# R2D2_Remote.net
KiCad netlist of a schematic drawn in EAGLE
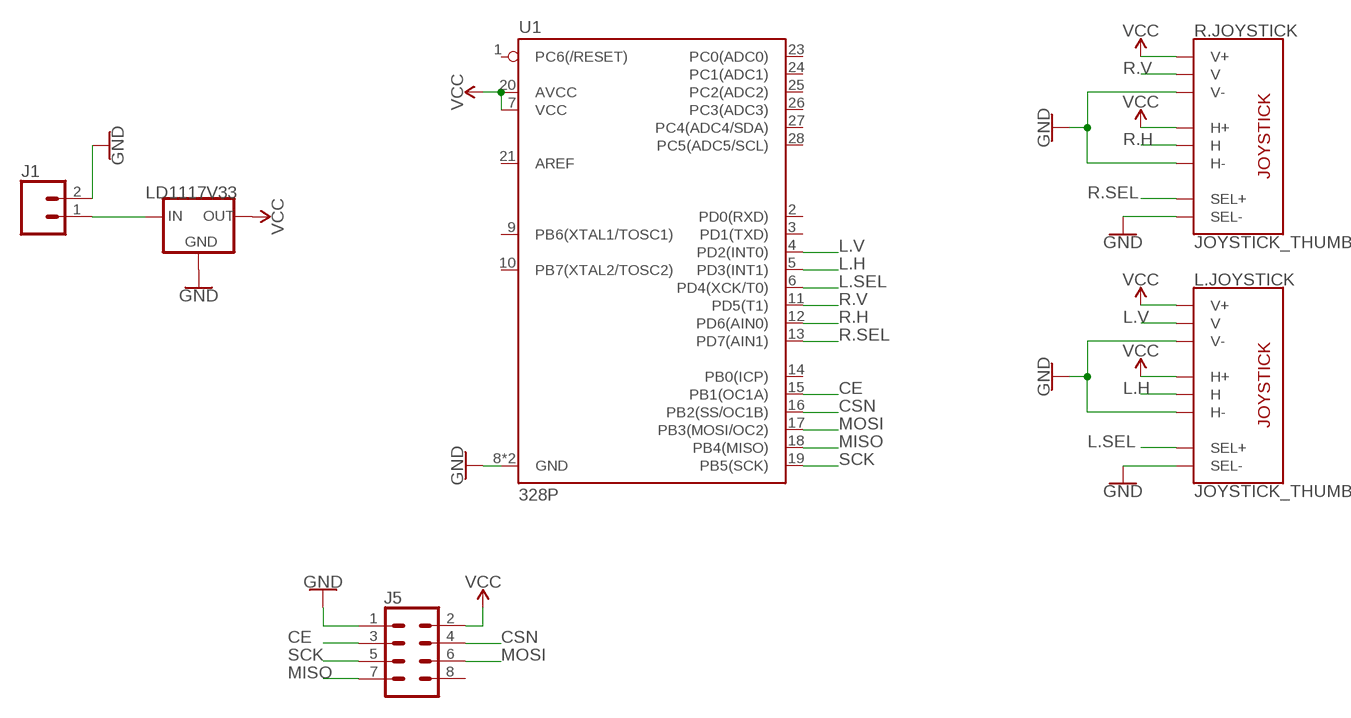
[diagram p0: schematic, sheet 1]

(export (version "E")
  (design (tool "Eeschema 10.0.6"))
  (components
    (comp (ref "J1")
      (value "CONN_02")
      (footprint "eagle-import:1X02")
      (libsource (lib "eagle-import") (part "CONN_02"))
    )
    (comp (ref "J5")
      (value "CONN_04X2")
      (footprint "eagle-import:2X4")
      (libsource (lib "eagle-import") (part "CONN_04X2"))
    )
    (comp (ref "L.JOYSTICK")
      (value "JOYSTICK_THUMB")
      (footprint "eagle-import:JOYSTICK")
      (libsource (lib "eagle-import") (part "JOYSTICK_THUMB"))
    )
    (comp (ref "R.JOYSTICK")
      (value "JOYSTICK_THUMB")
      (footprint "eagle-import:JOYSTICK")
      (libsource (lib "eagle-import") (part "JOYSTICK_THUMB"))
    )
    (comp (ref "U$1")
      (value "LD1117V33")
      (footprint "eagle-import:78XXL")
      (libsource (lib "eagle-import") (part "V_REG_LD1117VXX"))
    )
    (comp (ref "U1")
      (value "328P")
      (footprint "eagle-import:DIP28")
      (libsource (lib "eagle-import") (part "ATMEGA328P_PDIP"))
    )
  )
  (nets
    (net (code "1") (name "/CE") (class "Default")
      (node (ref "J5") (pin "3") (pinfunction "3_3") (pintype "passive"))
      (node (ref "U1") (pin "15") (pinfunction "PB1(OC1A)_15") (pintype "bidirectional"))
    )
    (net (code "2") (name "/CSN") (class "Default")
      (node (ref "J5") (pin "4") (pinfunction "4_4") (pintype "passive"))
      (node (ref "U1") (pin "16") (pinfunction "PB2(SS/OC1B)_16") (pintype "bidirectional"))
    )
    (net (code "3") (name "/L.H") (class "Default")
      (node (ref "L.JOYSTICK") (pin "H2") (pinfunction "H_H2") (pintype "bidirectional"))
      (node (ref "U1") (pin "5") (pinfunction "PD3(INT1)_5") (pintype "bidirectional"))
    )
    (net (code "4") (name "/L.SEL") (class "Default")
      (node (ref "L.JOYSTICK") (pin "B1A") (pinfunction "SEL+_B1A") (pintype "bidirectional"))
      (node (ref "U1") (pin "6") (pinfunction "PD4(XCK/T0)_6") (pintype "bidirectional"))
    )
    (net (code "5") (name "/L.V") (class "Default")
      (node (ref "L.JOYSTICK") (pin "V2") (pinfunction "V_V2") (pintype "bidirectional"))
      (node (ref "U1") (pin "4") (pinfunction "PD2(INT0)_4") (pintype "bidirectional"))
    )
    (net (code "6") (name "/MISO") (class "Default")
      (node (ref "J5") (pin "7") (pinfunction "7_7") (pintype "passive"))
      (node (ref "U1") (pin "18") (pinfunction "PB4(MISO)_18") (pintype "bidirectional"))
    )
    (net (code "7") (name "/MOSI") (class "Default")
      (node (ref "J5") (pin "6") (pinfunction "6_6") (pintype "passive"))
      (node (ref "U1") (pin "17") (pinfunction "PB3(MOSI/OC2)_17") (pintype "bidirectional"))
    )
    (net (code "8") (name "/R.H") (class "Default")
      (node (ref "R.JOYSTICK") (pin "H2") (pinfunction "H_H2") (pintype "bidirectional"))
      (node (ref "U1") (pin "12") (pinfunction "PD6(AIN0)_12") (pintype "bidirectional"))
    )
    (net (code "9") (name "/R.SEL") (class "Default")
      (node (ref "R.JOYSTICK") (pin "B1A") (pinfunction "SEL+_B1A") (pintype "bidirectional"))
      (node (ref "U1") (pin "13") (pinfunction "PD7(AIN1)_13") (pintype "bidirectional"))
    )
    (net (code "10") (name "/R.V") (class "Default")
      (node (ref "R.JOYSTICK") (pin "V2") (pinfunction "V_V2") (pintype "bidirectional"))
      (node (ref "U1") (pin "11") (pinfunction "PD5(T1)_11") (pintype "bidirectional"))
    )
    (net (code "11") (name "/SCK") (class "Default")
      (node (ref "J5") (pin "5") (pinfunction "5_5") (pintype "passive"))
      (node (ref "U1") (pin "19") (pinfunction "PB5(SCK)_19") (pintype "bidirectional"))
    )
    (net (code "12") (name "GND") (class "Default")
      (node (ref "J1") (pin "2") (pinfunction "2_2") (pintype "passive"))
      (node (ref "J5") (pin "1") (pinfunction "1_1") (pintype "passive"))
      (node (ref "L.JOYSTICK") (pin "B2A") (pinfunction "SEL-_B2A") (pintype "bidirectional"))
      (node (ref "L.JOYSTICK") (pin "H3") (pinfunction "H-_H3") (pintype "bidirectional"))
      (node (ref "L.JOYSTICK") (pin "V3") (pinfunction "V-_V3") (pintype "bidirectional"))
      (node (ref "R.JOYSTICK") (pin "B2A") (pinfunction "SEL-_B2A") (pintype "bidirectional"))
      (node (ref "R.JOYSTICK") (pin "H3") (pinfunction "H-_H3") (pintype "bidirectional"))
      (node (ref "R.JOYSTICK") (pin "V3") (pinfunction "V-_V3") (pintype "bidirectional"))
      (node (ref "U$1") (pin "IN") (pinfunction "GND_IN") (pintype "input"))
      (node (ref "U1") (pin "22") (pinfunction "GND_22") (pintype "bidirectional"))
      (node (ref "U1") (pin "8") (pinfunction "GND_8") (pintype "bidirectional"))
    )
    (net (code "13") (name "Net-(U$1-IN)") (class "Default")
      (node (ref "J1") (pin "1") (pinfunction "1_1") (pintype "passive"))
      (node (ref "U$1") (pin "OUT") (pinfunction "IN_OUT") (pintype "input"))
    )
    (net (code "14") (name "VCC") (class "Default")
      (node (ref "J5") (pin "2") (pinfunction "2_2") (pintype "passive"))
      (node (ref "L.JOYSTICK") (pin "H1") (pinfunction "H+_H1") (pintype "bidirectional"))
      (node (ref "L.JOYSTICK") (pin "V1") (pinfunction "V+_V1") (pintype "bidirectional"))
      (node (ref "R.JOYSTICK") (pin "H1") (pinfunction "H+_H1") (pintype "bidirectional"))
      (node (ref "R.JOYSTICK") (pin "V1") (pinfunction "V+_V1") (pintype "bidirectional"))
      (node (ref "U$1") (pin "GND") (pinfunction "OUT_GND") (pintype "passive"))
      (node (ref "U1") (pin "20") (pinfunction "AVCC_20") (pintype "bidirectional"))
      (node (ref "U1") (pin "7") (pinfunction "VCC_7") (pintype "bidirectional"))
    )
    (net (code "15") (name "unconnected-(J5-Pad8)") (class "Default")
      (node (ref "J5") (pin "8") (pinfunction "8_8") (pintype "passive"))
    )
    (net (code "16") (name "unconnected-(U1-AREF-Pad21)") (class "Default")
      (node (ref "U1") (pin "21") (pinfunction "AREF_21") (pintype "bidirectional"))
    )
    (net (code "17") (name "unconnected-(U1-PB0(ICP)-Pad14)") (class "Default")
      (node (ref "U1") (pin "14") (pinfunction "PB0(ICP)_14") (pintype "bidirectional"))
    )
    (net (code "18") (name "unconnected-(U1-PB6(XTAL1{slash}TOSC1)-Pad9)") (class "Default")
      (node (ref "U1") (pin "9") (pinfunction "PB6(XTAL1/TOSC1)_9") (pintype "bidirectional"))
    )
    (net (code "19") (name "unconnected-(U1-PB7(XTAL2{slash}TOSC2)-Pad10)") (class "Default")
      (node (ref "U1") (pin "10") (pinfunction "PB7(XTAL2/TOSC2)_10") (pintype "bidirectional"))
    )
    (net (code "20") (name "unconnected-(U1-PC0(ADC0)-Pad23)") (class "Default")
      (node (ref "U1") (pin "23") (pinfunction "PC0(ADC0)_23") (pintype "bidirectional"))
    )
    (net (code "21") (name "unconnected-(U1-PC1(ADC1)-Pad24)") (class "Default")
      (node (ref "U1") (pin "24") (pinfunction "PC1(ADC1)_24") (pintype "bidirectional"))
    )
    (net (code "22") (name "unconnected-(U1-PC2(ADC2)-Pad25)") (class "Default")
      (node (ref "U1") (pin "25") (pinfunction "PC2(ADC2)_25") (pintype "bidirectional"))
    )
    (net (code "23") (name "unconnected-(U1-PC3(ADC3)-Pad26)") (class "Default")
      (node (ref "U1") (pin "26") (pinfunction "PC3(ADC3)_26") (pintype "bidirectional"))
    )
    (net (code "24") (name "unconnected-(U1-PC4(ADC4{slash}SDA)-Pad27)") (class "Default")
      (node (ref "U1") (pin "27") (pinfunction "PC4(ADC4/SDA)_27") (pintype "bidirectional"))
    )
    (net (code "25") (name "unconnected-(U1-PC5(ADC5{slash}SCL)-Pad28)") (class "Default")
      (node (ref "U1") (pin "28") (pinfunction "PC5(ADC5/SCL)_28") (pintype "bidirectional"))
    )
    (net (code "26") (name "unconnected-(U1-PC6({slash}RESET)-Pad1)") (class "Default")
      (node (ref "U1") (pin "1") (pinfunction "PC6(/RESET)_1") (pintype "bidirectional"))
    )
    (net (code "27") (name "unconnected-(U1-PD0(RXD)-Pad2)") (class "Default")
      (node (ref "U1") (pin "2") (pinfunction "PD0(RXD)_2") (pintype "bidirectional"))
    )
    (net (code "28") (name "unconnected-(U1-PD1(TXD)-Pad3)") (class "Default")
      (node (ref "U1") (pin "3") (pinfunction "PD1(TXD)_3") (pintype "bidirectional"))
    )
  )
)
